# Mics.net
KiCad netlist of a schematic drawn in Altium Designer
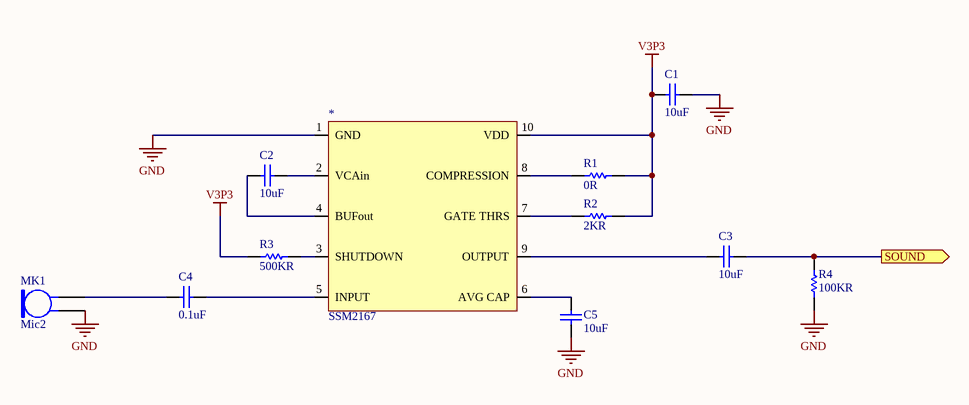
[diagram p0: Mics.SchDoc]

(export (version "E")
  (design (tool "Eeschema 10.0.6"))
  (components
    (comp (ref "*") (value "SSM2167") (libsource (lib "SCHLIB_Autobot") (part "SSM2167")))
    (comp (ref "C1")
      (value "10uF")
      (footprint "RAD-0.3")
      (description "Capacitor")
      (fields (field (name "PUBLISHER") "Altium Limited"))
      (libsource (lib "Miscellaneous Devices") (part "Cap"))
    )
    (comp (ref "C2")
      (value "10uF")
      (footprint "RAD-0.3")
      (description "Capacitor")
      (fields (field (name "PUBLISHER") "Altium Limited"))
      (libsource (lib "Miscellaneous Devices") (part "Cap"))
    )
    (comp (ref "C3")
      (value "10uF")
      (footprint "RAD-0.3")
      (description "Capacitor")
      (fields (field (name "PUBLISHER") "Altium Limited"))
      (libsource (lib "Miscellaneous Devices") (part "Cap"))
    )
    (comp (ref "C4")
      (value "0.1uF")
      (footprint "RAD-0.3")
      (description "Capacitor")
      (fields (field (name "PUBLISHER") "Altium Limited"))
      (libsource (lib "Miscellaneous Devices") (part "Cap"))
    )
    (comp (ref "C5")
      (value "10uF")
      (footprint "RAD-0.3")
      (description "Capacitor")
      (fields (field (name "PUBLISHER") "Altium Limited"))
      (libsource (lib "Miscellaneous Devices") (part "Cap"))
    )
    (comp (ref "MK1")
      (value "Mic2")
      (footprint "PIN2")
      (description "Microphone")
      (fields (field (name "PUBLISHER") "Altium Limited"))
      (libsource (lib "Miscellaneous Devices") (part "Mic2"))
    )
    (comp (ref "R1")
      (value "0R")
      (footprint "AXIAL-0.3")
      (description "Resistor")
      (fields (field (name "PUBLISHER") "Altium Limited"))
      (libsource (lib "Miscellaneous Devices") (part "Res1"))
    )
    (comp (ref "R2")
      (value "2KR")
      (footprint "AXIAL-0.3")
      (description "Resistor")
      (fields (field (name "PUBLISHER") "Altium Limited"))
      (libsource (lib "Miscellaneous Devices") (part "Res1"))
    )
    (comp (ref "R3")
      (value "500KR")
      (footprint "AXIAL-0.3")
      (description "Resistor")
      (fields (field (name "PUBLISHER") "Altium Limited"))
      (libsource (lib "Miscellaneous Devices") (part "Res1"))
    )
    (comp (ref "R4")
      (value "100KR")
      (footprint "AXIAL-0.3")
      (description "Resistor")
      (fields (field (name "PUBLISHER") "Altium Limited"))
      (libsource (lib "Miscellaneous Devices") (part "Res1"))
    )
  )
  (nets
    (net (code "1") (name "/SOUND") (class "Default")
      (node (ref "C3") (pin "1") (pinfunction "1_1") (pintype "passive"))
      (node (ref "R4") (pin "2") (pinfunction "2_2") (pintype "passive"))
    )
    (net (code "2") (name "GND") (class "Default")
      (node (ref "*") (pin "1") (pinfunction "GND_1") (pintype "passive"))
      (node (ref "C1") (pin "1") (pinfunction "1_1") (pintype "passive"))
      (node (ref "C5") (pin "2") (pinfunction "2_2") (pintype "passive"))
      (node (ref "MK1") (pin "1") (pinfunction "1_1") (pintype "passive"))
      (node (ref "R4") (pin "1") (pinfunction "1_1") (pintype "passive"))
    )
    (net (code "3") (name "Net-(*-AVG_CAP)") (class "Default")
      (node (ref "*") (pin "6") (pinfunction "AVG_CAP_6") (pintype "passive"))
      (node (ref "C5") (pin "1") (pinfunction "1_1") (pintype "passive"))
    )
    (net (code "4") (name "Net-(*-BUFout)") (class "Default")
      (node (ref "*") (pin "4") (pinfunction "BUFout_4") (pintype "passive"))
      (node (ref "C2") (pin "2") (pinfunction "2_2") (pintype "passive"))
    )
    (net (code "5") (name "Net-(*-COMPRESSION)") (class "Default")
      (node (ref "*") (pin "8") (pinfunction "COMPRESSION_8") (pintype "passive"))
      (node (ref "R1") (pin "2") (pinfunction "2_2") (pintype "passive"))
    )
    (net (code "6") (name "Net-(*-GATE_THRS)") (class "Default")
      (node (ref "*") (pin "7") (pinfunction "GATE_THRS_7") (pintype "passive"))
      (node (ref "R2") (pin "2") (pinfunction "2_2") (pintype "passive"))
    )
    (net (code "7") (name "Net-(*-INPUT)") (class "Default")
      (node (ref "*") (pin "5") (pinfunction "INPUT_5") (pintype "passive"))
      (node (ref "C4") (pin "2") (pinfunction "2_2") (pintype "passive"))
    )
    (net (code "8") (name "Net-(*-OUTPUT)") (class "Default")
      (node (ref "*") (pin "9") (pinfunction "OUTPUT_9") (pintype "passive"))
      (node (ref "C3") (pin "2") (pinfunction "2_2") (pintype "passive"))
    )
    (net (code "9") (name "Net-(*-SHUTDOWN)") (class "Default")
      (node (ref "*") (pin "3") (pinfunction "SHUTDOWN_3") (pintype "passive"))
      (node (ref "R3") (pin "1") (pinfunction "1_1") (pintype "passive"))
    )
    (net (code "10") (name "Net-(*-VCAin)") (class "Default")
      (node (ref "*") (pin "2") (pinfunction "VCAin_2") (pintype "passive"))
      (node (ref "C2") (pin "1") (pinfunction "1_1") (pintype "passive"))
    )
    (net (code "11") (name "Net-(C4-Pad1)") (class "Default")
      (node (ref "C4") (pin "1") (pinfunction "1_1") (pintype "passive"))
      (node (ref "MK1") (pin "2") (pinfunction "2_2") (pintype "passive"))
    )
    (net (code "12") (name "V3P3") (class "Default")
      (node (ref "*") (pin "10") (pinfunction "VDD_10") (pintype "passive"))
      (node (ref "C1") (pin "2") (pinfunction "2_2") (pintype "passive"))
      (node (ref "R1") (pin "1") (pinfunction "1_1") (pintype "passive"))
      (node (ref "R2") (pin "1") (pinfunction "1_1") (pintype "passive"))
      (node (ref "R3") (pin "2") (pinfunction "2_2") (pintype "passive"))
    )
  )
)
